# LED_Keychain.net
KiCad netlist of a schematic drawn in EAGLE
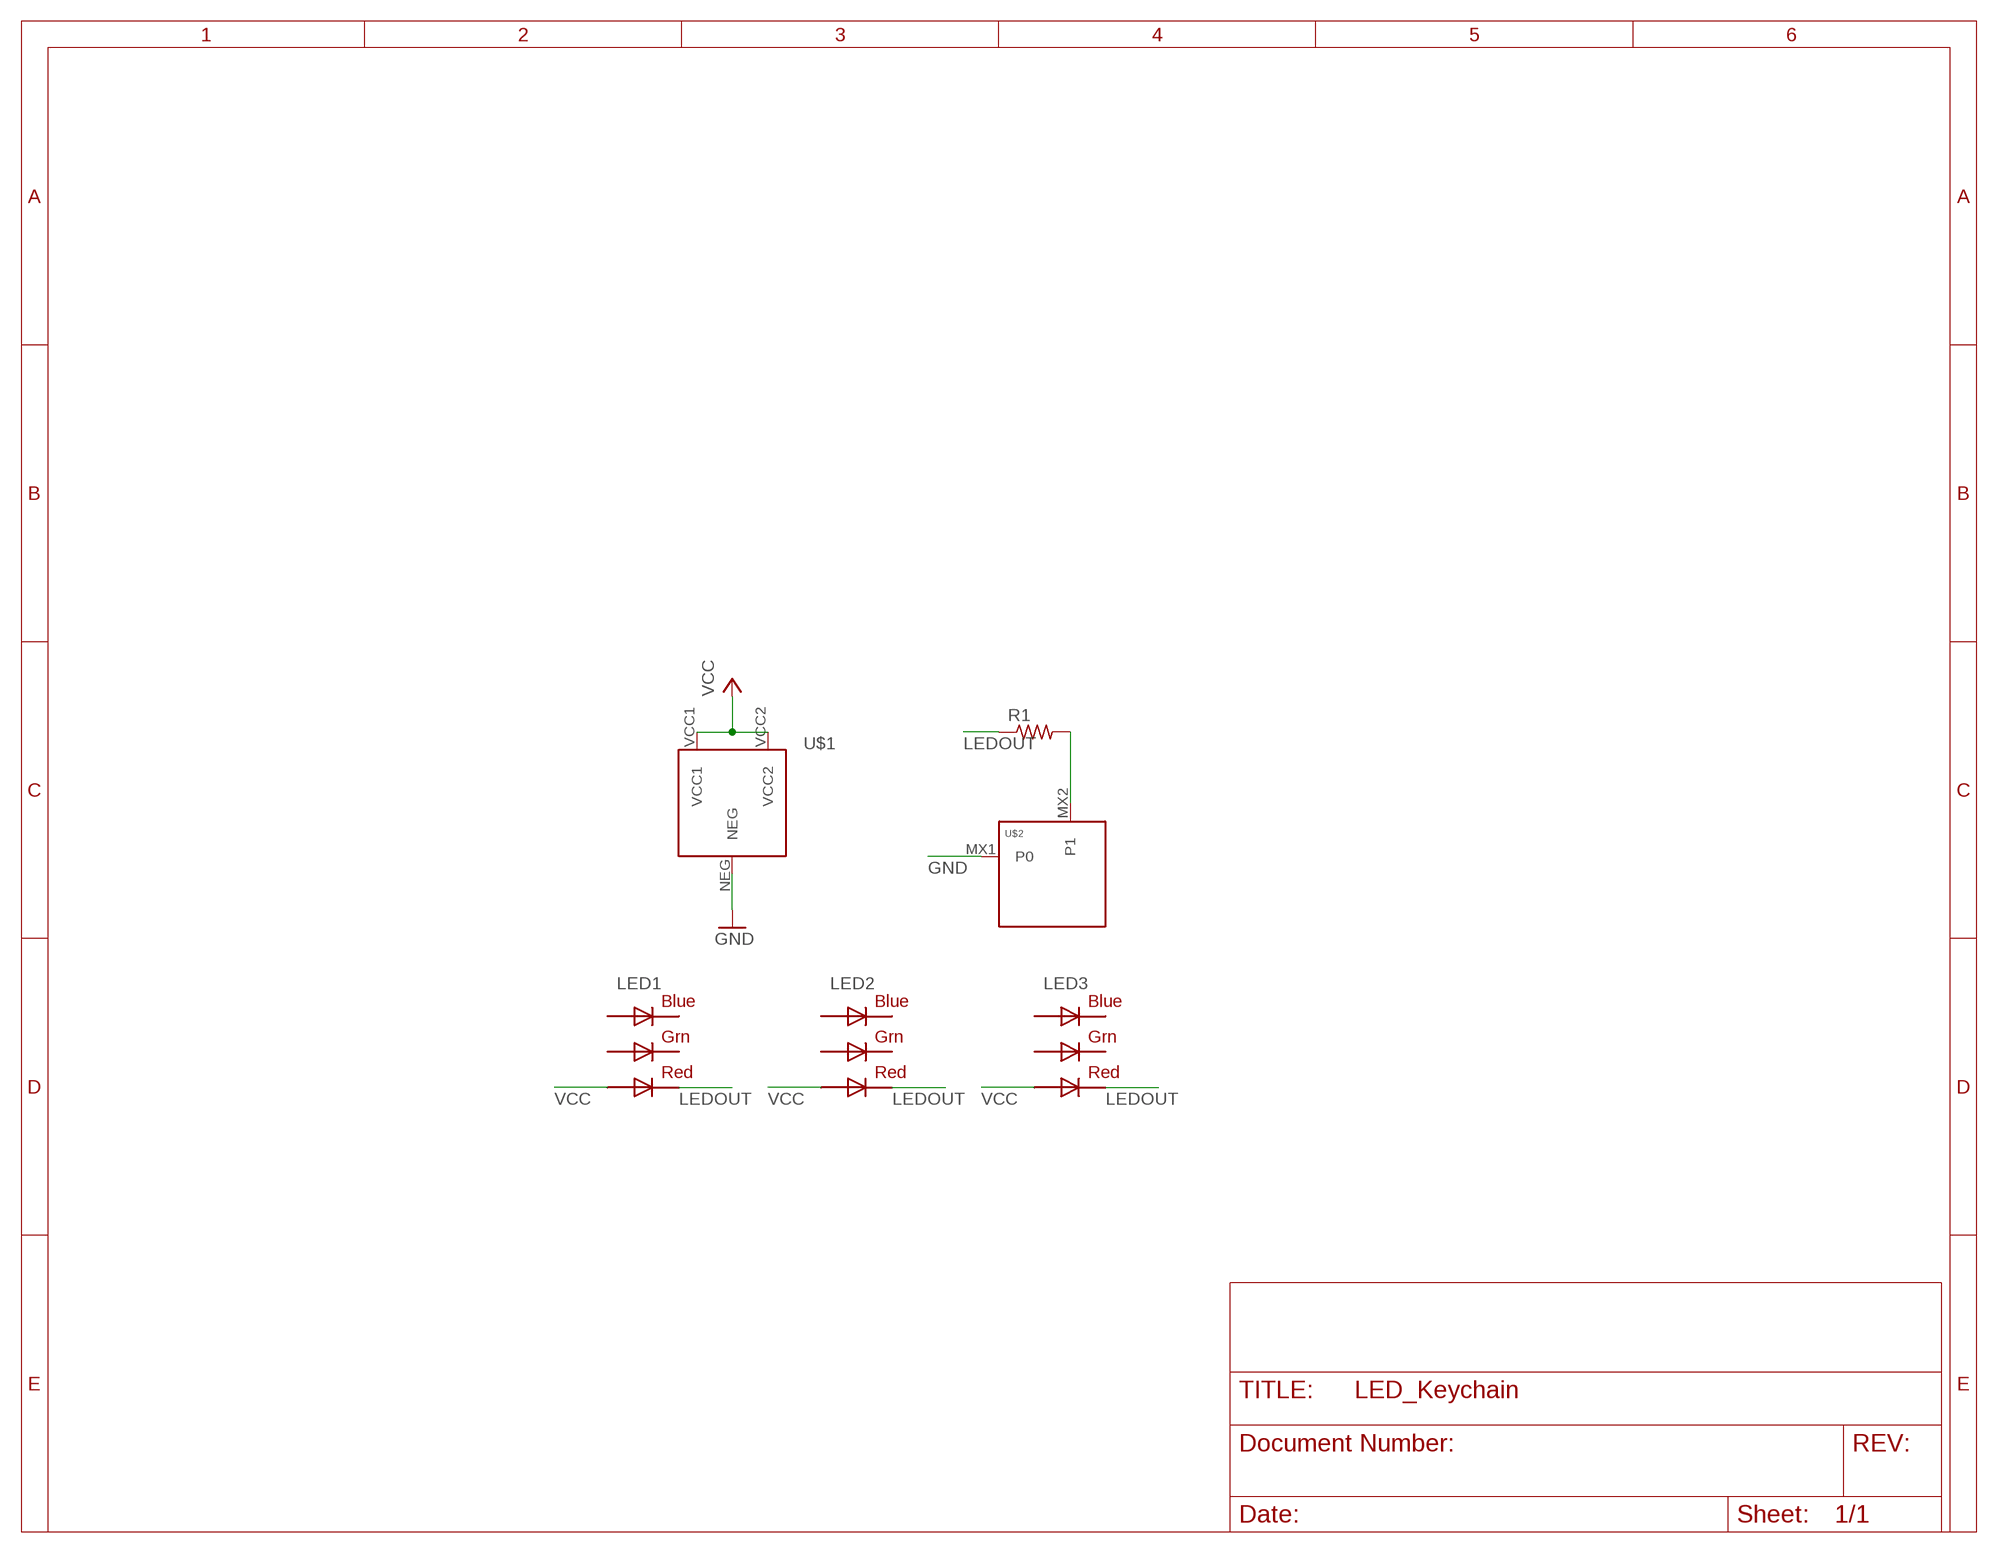
[diagram p0: schematic, sheet 1]

(export (version "E")
  (design (tool "Eeschema 10.0.6"))
  (components
    (comp (ref "LED1")
      (value "RGBLED5050")
      (footprint "eagle-import:RGBLED5050")
      (libsource (lib "eagle-import") (part "RGBLED5050"))
    )
    (comp (ref "LED2")
      (value "RGBLED5050")
      (footprint "eagle-import:RGBLED5050")
      (libsource (lib "eagle-import") (part "RGBLED5050"))
    )
    (comp (ref "LED3")
      (value "RGBLED5050")
      (footprint "eagle-import:RGBLED5050")
      (libsource (lib "eagle-import") (part "RGBLED5050"))
    )
    (comp (ref "R1")
      (value "R-US_R0603")
      (footprint "eagle-import:R0603")
      (libsource (lib "eagle-import") (part "R-US_R0603"))
    )
    (comp (ref "U$1")
      (value "KEYSTONE3035")
      (footprint "eagle-import:KEYSTONE3035")
      (libsource (lib "eagle-import") (part "KEYSTONE3035"))
    )
    (comp (ref "U$2")
      (value "KEYSWITCH-PLAIN-MX-1U")
      (footprint "eagle-import:MX-1U")
      (libsource (lib "eagle-import") (part "KEYSWITCH-PLAIN-MX-1U"))
    )
  )
  (nets
    (net (code "1") (name "/LEDOUT") (class "Default")
      (node (ref "LED1") (pin "5") (pinfunction "RED_C_5") (pintype "bidirectional"))
      (node (ref "LED2") (pin "5") (pinfunction "RED_C_5") (pintype "bidirectional"))
      (node (ref "LED3") (pin "5") (pinfunction "RED_C_5") (pintype "bidirectional"))
      (node (ref "R1") (pin "1") (pinfunction "1_1") (pintype "passive"))
    )
    (net (code "2") (name "GND") (class "Default")
      (node (ref "U$1") (pin "NEG") (pinfunction "NEG_NEG") (pintype "bidirectional"))
      (node (ref "U$2") (pin "MX1") (pinfunction "P0_MX1") (pintype "bidirectional"))
    )
    (net (code "3") (name "Net-(U$2-P1)") (class "Default")
      (node (ref "R1") (pin "2") (pinfunction "2_2") (pintype "passive"))
      (node (ref "U$2") (pin "MX2") (pinfunction "P1_MX2") (pintype "bidirectional"))
    )
    (net (code "4") (name "VCC") (class "Default")
      (node (ref "LED1") (pin "2") (pinfunction "RED_A_2") (pintype "bidirectional"))
      (node (ref "LED2") (pin "2") (pinfunction "RED_A_2") (pintype "bidirectional"))
      (node (ref "LED3") (pin "2") (pinfunction "RED_A_2") (pintype "bidirectional"))
      (node (ref "U$1") (pin "VCC1") (pinfunction "VCC1_VCC1") (pintype "bidirectional"))
      (node (ref "U$1") (pin "VCC2") (pinfunction "VCC2_VCC2") (pintype "bidirectional"))
    )
    (net (code "5") (name "unconnected-(LED1-BLUE_A-Pad3)") (class "Default")
      (node (ref "LED1") (pin "3") (pinfunction "BLUE_A_3") (pintype "bidirectional"))
    )
    (net (code "6") (name "unconnected-(LED1-BLUE_C-Pad4)") (class "Default")
      (node (ref "LED1") (pin "4") (pinfunction "BLUE_C_4") (pintype "bidirectional"))
    )
    (net (code "7") (name "unconnected-(LED1-GREEN_A-Pad1)") (class "Default")
      (node (ref "LED1") (pin "1") (pinfunction "GREEN_A_1") (pintype "bidirectional"))
    )
    (net (code "8") (name "unconnected-(LED1-GREEN_C-Pad6)") (class "Default")
      (node (ref "LED1") (pin "6") (pinfunction "GREEN_C_6") (pintype "bidirectional"))
    )
    (net (code "9") (name "unconnected-(LED2-BLUE_A-Pad3)") (class "Default")
      (node (ref "LED2") (pin "3") (pinfunction "BLUE_A_3") (pintype "bidirectional"))
    )
    (net (code "10") (name "unconnected-(LED2-BLUE_C-Pad4)") (class "Default")
      (node (ref "LED2") (pin "4") (pinfunction "BLUE_C_4") (pintype "bidirectional"))
    )
    (net (code "11") (name "unconnected-(LED2-GREEN_A-Pad1)") (class "Default")
      (node (ref "LED2") (pin "1") (pinfunction "GREEN_A_1") (pintype "bidirectional"))
    )
    (net (code "12") (name "unconnected-(LED2-GREEN_C-Pad6)") (class "Default")
      (node (ref "LED2") (pin "6") (pinfunction "GREEN_C_6") (pintype "bidirectional"))
    )
    (net (code "13") (name "unconnected-(LED3-BLUE_A-Pad3)") (class "Default")
      (node (ref "LED3") (pin "3") (pinfunction "BLUE_A_3") (pintype "bidirectional"))
    )
    (net (code "14") (name "unconnected-(LED3-BLUE_C-Pad4)") (class "Default")
      (node (ref "LED3") (pin "4") (pinfunction "BLUE_C_4") (pintype "bidirectional"))
    )
    (net (code "15") (name "unconnected-(LED3-GREEN_A-Pad1)") (class "Default")
      (node (ref "LED3") (pin "1") (pinfunction "GREEN_A_1") (pintype "bidirectional"))
    )
    (net (code "16") (name "unconnected-(LED3-GREEN_C-Pad6)") (class "Default")
      (node (ref "LED3") (pin "6") (pinfunction "GREEN_C_6") (pintype "bidirectional"))
    )
  )
)
